# BOOT_JTAG_AUX.net
KiCad netlist of a schematic drawn in Altium Designer
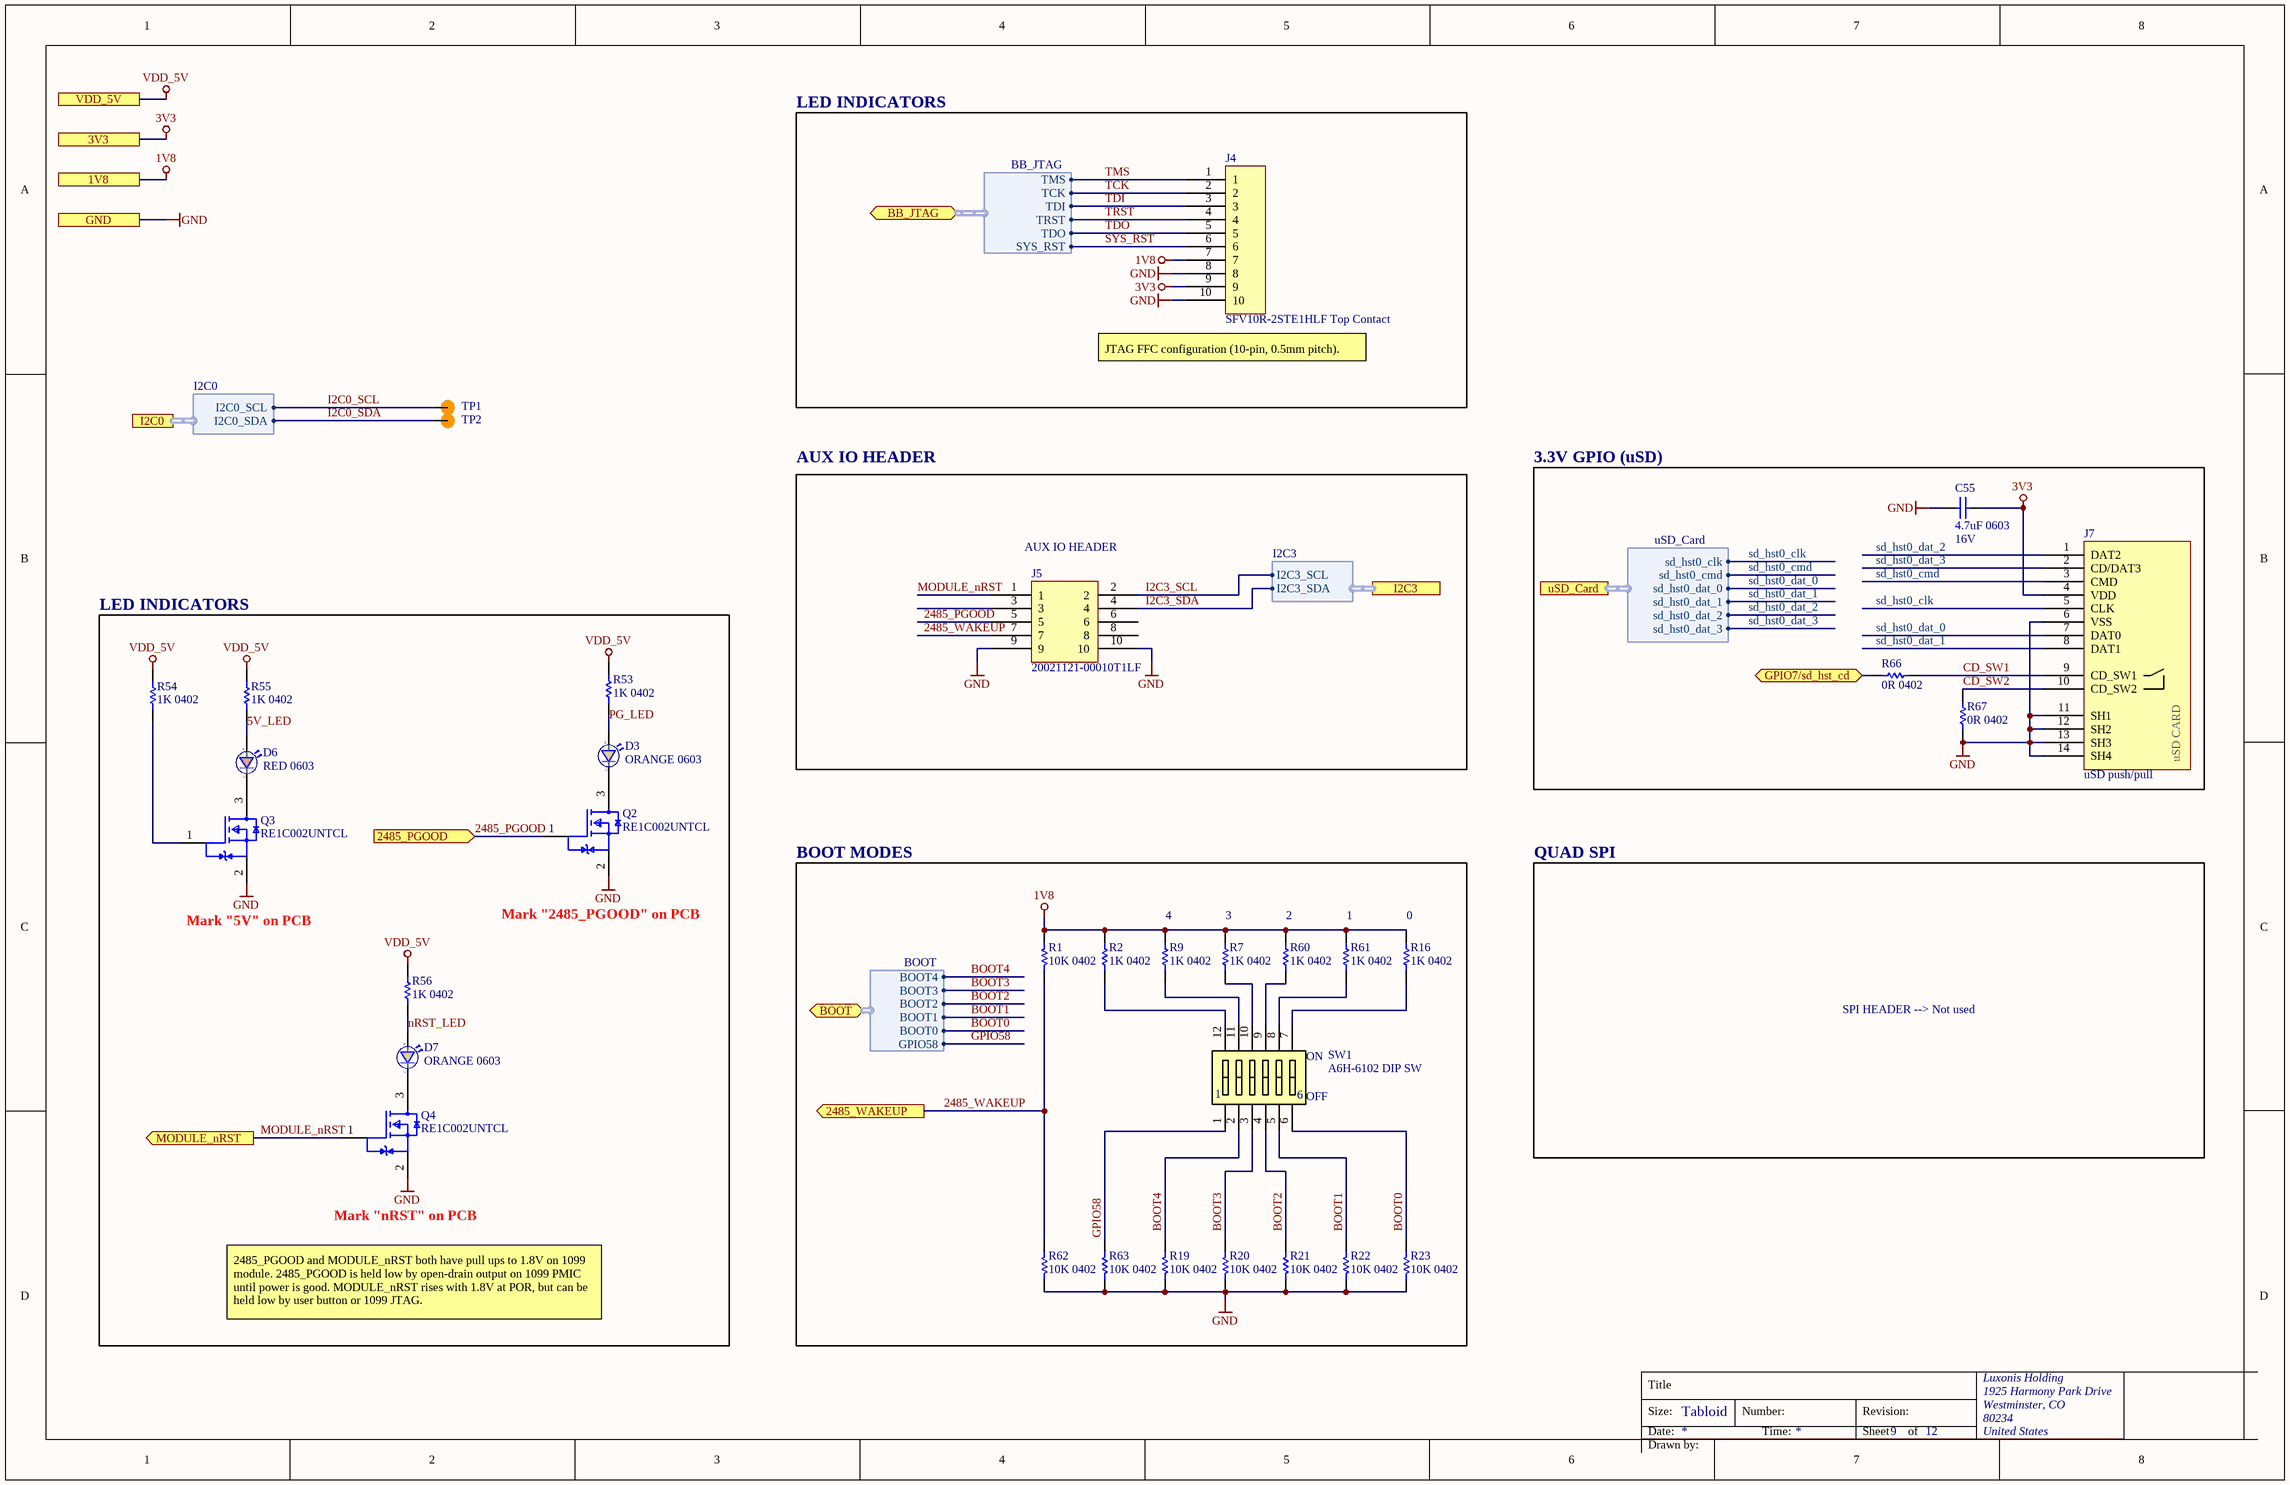
[diagram p0: BOOT_JTAG_AUX.SchDoc]

(export (version "E")
  (design (tool "Eeschema 10.0.6"))
  (components
    (comp (ref "C55")
      (value "4.7uF 0603")
      (footprint "CAP_Altium_Vault_Generic:CAPC0603(1608)100_N")
      (description "CAP CER 4.7UF 16V X5R 0603 10%")
      (fields (field (name "TOLERANCE") "10%") (field (name "VOLTAGE RATING") "16V"))
      (libsource (lib "LuxonisMaster") (part "GRM188R61C475KAAJD"))
    )
    (comp (ref "D3")
      (value "ORANGE 0603")
      (footprint "LuxonisMaster:SML_D1xx8W")
      (description "LED ORANGE DIFFUSED 0603 SMD Orange 605nm LED Indication - Discrete 2.2V 0603 (1608 Metric)")
      (libsource (lib "LuxonisMaster") (part "SML-D12D8WT86"))
    )
    (comp (ref "D6")
      (value "RED 0603")
      (footprint "LuxonisMaster:SML_D1xx8W")
      (description "LED RED DIFFUSED 0603 SMD Red 620nm LED Indication - Discrete 2.2V 0603 (1608 Metric)")
      (libsource (lib "LuxonisMaster") (part "SML-D12U8WT86"))
    )
    (comp (ref "D7")
      (value "ORANGE 0603")
      (footprint "LuxonisMaster:SML_D1xx8W")
      (description "LED ORANGE DIFFUSED 0603 SMD Orange 605nm LED Indication - Discrete 2.2V 0603 (1608 Metric)")
      (libsource (lib "LuxonisMaster") (part "SML-D12D8WT86"))
    )
    (comp (ref "J4")
      (value "SFV10R-2STE1HLF Top Contact")
      (footprint "LuxonisMaster:SFV10R-2STE1HLF")
      (description "CONN FFC TOP 10POS 0.50MM R/A")
      (libsource (lib "LuxonisMaster") (part "SFV10R-2STE1HLF"))
    )
    (comp (ref "J5")
      (value "20021121-00010T1LF")
      (footprint "LuxonisMaster:20021121-00010T1LF")
      (description "CONN HEADER SMD 10POS 1.27MM")
      (libsource (lib "LuxonisMaster") (part "20021121-00010T1LF"))
    )
    (comp (ref "J7")
      (value "uSD push/pull")
      (footprint "LuxonisMaster:104031-0811")
      (description "CONN MICRO SD CARD PUSH-PULL R/A")
      (libsource (lib "LuxonisMaster") (part "104031-0811"))
    )
    (comp (ref "Q2")
      (value "RE1C002UNTCL")
      (footprint "LuxonisMaster:RE1C002UNTCL")
      (description "MOSFET N-CH 20V 0.2A EMT3")
      (libsource (lib "LuxonisMaster") (part "RE1C002UNTCL"))
    )
    (comp (ref "Q3")
      (value "RE1C002UNTCL")
      (footprint "LuxonisMaster:RE1C002UNTCL")
      (description "MOSFET N-CH 20V 0.2A EMT3")
      (libsource (lib "LuxonisMaster") (part "RE1C002UNTCL"))
    )
    (comp (ref "Q4")
      (value "RE1C002UNTCL")
      (footprint "LuxonisMaster:RE1C002UNTCL")
      (description "MOSFET N-CH 20V 0.2A EMT3")
      (libsource (lib "LuxonisMaster") (part "RE1C002UNTCL"))
    )
    (comp (ref "R1")
      (value "10K 0402")
      (footprint "RES_Altium_Vault_Generic:RESC0402(1005)_N")
      (fields (field (name "TOLERANCE") "1%"))
      (libsource (lib "LuxonisMaster") (part "RC0402FR-1310KL"))
    )
    (comp (ref "R2")
      (value "1K 0402")
      (footprint "RES_Altium_Vault_Generic:RESC0402(1005)_N")
      (fields (field (name "TOLERANCE") "1%"))
      (libsource (lib "LuxonisMaster") (part "RC0402FR-071KL"))
    )
    (comp (ref "R7")
      (value "1K 0402")
      (footprint "RES_Altium_Vault_Generic:RESC0402(1005)_N")
      (fields (field (name "TOLERANCE") "1%"))
      (libsource (lib "LuxonisMaster") (part "RC0402FR-071KL"))
    )
    (comp (ref "R9")
      (value "1K 0402")
      (footprint "RES_Altium_Vault_Generic:RESC0402(1005)_N")
      (fields (field (name "TOLERANCE") "1%"))
      (libsource (lib "LuxonisMaster") (part "RC0402FR-071KL"))
    )
    (comp (ref "R16")
      (value "1K 0402")
      (footprint "RES_Altium_Vault_Generic:RESC0402(1005)_N")
      (fields (field (name "TOLERANCE") "1%"))
      (libsource (lib "LuxonisMaster") (part "RC0402FR-071KL"))
    )
    (comp (ref "R19")
      (value "10K 0402")
      (footprint "RES_Altium_Vault_Generic:RESC0402(1005)_N")
      (fields (field (name "TOLERANCE") "1%"))
      (libsource (lib "LuxonisMaster") (part "RC0402FR-1310KL"))
    )
    (comp (ref "R20")
      (value "10K 0402")
      (footprint "RES_Altium_Vault_Generic:RESC0402(1005)_N")
      (fields (field (name "TOLERANCE") "1%"))
      (libsource (lib "LuxonisMaster") (part "RC0402FR-1310KL"))
    )
    (comp (ref "R21")
      (value "10K 0402")
      (footprint "RES_Altium_Vault_Generic:RESC0402(1005)_N")
      (fields (field (name "TOLERANCE") "1%"))
      (libsource (lib "LuxonisMaster") (part "RC0402FR-1310KL"))
    )
    (comp (ref "R22")
      (value "10K 0402")
      (footprint "RES_Altium_Vault_Generic:RESC0402(1005)_N")
      (fields (field (name "TOLERANCE") "1%"))
      (libsource (lib "LuxonisMaster") (part "RC0402FR-1310KL"))
    )
    (comp (ref "R23")
      (value "10K 0402")
      (footprint "RES_Altium_Vault_Generic:RESC0402(1005)_N")
      (fields (field (name "TOLERANCE") "1%"))
      (libsource (lib "LuxonisMaster") (part "RC0402FR-1310KL"))
    )
    (comp (ref "R53")
      (value "1K 0402")
      (footprint "RES_Altium_Vault_Generic:RESC0402(1005)_N")
      (fields (field (name "TOLERANCE") "1%"))
      (libsource (lib "LuxonisMaster") (part "RC0402FR-071KL"))
    )
    (comp (ref "R54")
      (value "1K 0402")
      (footprint "RES_Altium_Vault_Generic:RESC0402(1005)_N")
      (fields (field (name "TOLERANCE") "1%"))
      (libsource (lib "LuxonisMaster") (part "RC0402FR-071KL"))
    )
    (comp (ref "R55")
      (value "1K 0402")
      (footprint "RES_Altium_Vault_Generic:RESC0402(1005)_N")
      (fields (field (name "TOLERANCE") "1%"))
      (libsource (lib "LuxonisMaster") (part "RC0402FR-071KL"))
    )
    (comp (ref "R56")
      (value "1K 0402")
      (footprint "RES_Altium_Vault_Generic:RESC0402(1005)_N")
      (fields (field (name "TOLERANCE") "1%"))
      (libsource (lib "LuxonisMaster") (part "RC0402FR-071KL"))
    )
    (comp (ref "R60")
      (value "1K 0402")
      (footprint "RES_Altium_Vault_Generic:RESC0402(1005)_N")
      (fields (field (name "TOLERANCE") "1%"))
      (libsource (lib "LuxonisMaster") (part "RC0402FR-071KL"))
    )
    (comp (ref "R61")
      (value "1K 0402")
      (footprint "RES_Altium_Vault_Generic:RESC0402(1005)_N")
      (fields (field (name "TOLERANCE") "1%"))
      (libsource (lib "LuxonisMaster") (part "RC0402FR-071KL"))
    )
    (comp (ref "R62")
      (value "10K 0402")
      (footprint "RES_Altium_Vault_Generic:RESC0402(1005)_N")
      (fields (field (name "TOLERANCE") "1%"))
      (libsource (lib "LuxonisMaster") (part "RC0402FR-1310KL"))
    )
    (comp (ref "R63")
      (value "10K 0402")
      (footprint "RES_Altium_Vault_Generic:RESC0402(1005)_N")
      (fields (field (name "TOLERANCE") "1%"))
      (libsource (lib "LuxonisMaster") (part "RC0402FR-1310KL"))
    )
    (comp (ref "R66")
      (value "0R 0402")
      (footprint "RES_Altium_Vault_Generic:RESC0402(1005)_N")
      (description "RES SMD 0 OHM JUMPER 1/16W 0402")
      (fields (field (name "TOLERANCE") "5%"))
      (libsource (lib "LuxonisMaster") (part "CRCW04020000Z0ED"))
    )
    (comp (ref "R67")
      (value "0R 0402")
      (footprint "RES_Altium_Vault_Generic:RESC0402(1005)_N")
      (description "RES SMD 0 OHM JUMPER 1/16W 0402")
      (fields (field (name "TOLERANCE") "5%"))
      (libsource (lib "LuxonisMaster") (part "CRCW04020000Z0ED"))
    )
    (comp (ref "SW1")
      (value "A6H-6102 DIP SW")
      (footprint "LuxonisMaster:A6H-610x")
      (description "SWITCH SLIDE DIP SPST 25MA 24V (SEALED)")
      (libsource (lib "LuxonisMaster") (part "A6H-6102"))
    )
    (comp (ref "TP1")
      (value "TP100_200_NS")
      (footprint "LuxonisMaster:TP100_200_NS")
      (libsource (lib "LuxonisMaster") (part "TEST_POINT"))
    )
    (comp (ref "TP2")
      (value "TP100_200_NS")
      (footprint "LuxonisMaster:TP100_200_NS")
      (libsource (lib "LuxonisMaster") (part "TEST_POINT"))
    )
  )
  (nets
    (net (code "6") (name "/5V_LED") (class "Default")
      (node (ref "D6") (pin "2") (pinfunction "A_2") (pintype "passive"))
      (node (ref "R55") (pin "1") (pinfunction "1_1") (pintype "passive"))
    )
    (net (code "7") (name "/2485_PGOOD") (class "Default")
      (node (ref "J5") (pin "5") (pinfunction "5_5") (pintype "passive"))
      (node (ref "Q2") (pin "1") (pinfunction "Gate_1") (pintype "passive"))
    )
    (net (code "8") (name "/2485_WAKEUP") (class "Default")
      (node (ref "J5") (pin "7") (pinfunction "7_7") (pintype "passive"))
      (node (ref "R1") (pin "2") (pinfunction "2_2") (pintype "passive"))
      (node (ref "R62") (pin "1") (pinfunction "1_1") (pintype "passive"))
    )
    (net (code "9") (name "/BOOT0") (class "Default")
      (node (ref "R23") (pin "1") (pinfunction "1_1") (pintype "passive"))
      (node (ref "SW1") (pin "6") (pinfunction "6_6") (pintype "passive"))
    )
    (net (code "10") (name "/BOOT1") (class "Default")
      (node (ref "R22") (pin "1") (pinfunction "1_1") (pintype "passive"))
      (node (ref "SW1") (pin "5") (pinfunction "5_5") (pintype "passive"))
    )
    (net (code "11") (name "/BOOT2") (class "Default")
      (node (ref "R21") (pin "1") (pinfunction "1_1") (pintype "passive"))
      (node (ref "SW1") (pin "4") (pinfunction "4_4") (pintype "passive"))
    )
    (net (code "12") (name "/BOOT3") (class "Default")
      (node (ref "R20") (pin "1") (pinfunction "1_1") (pintype "passive"))
      (node (ref "SW1") (pin "3") (pinfunction "3_3") (pintype "passive"))
    )
    (net (code "13") (name "/BOOT4") (class "Default")
      (node (ref "R19") (pin "1") (pinfunction "1_1") (pintype "passive"))
      (node (ref "SW1") (pin "2") (pinfunction "2_2") (pintype "passive"))
    )
    (net (code "14") (name "/CD_SW1") (class "Default")
      (node (ref "J7") (pin "9") (pinfunction "CD_SW1_9") (pintype "passive"))
      (node (ref "R66") (pin "1") (pinfunction "1_1") (pintype "passive"))
    )
    (net (code "15") (name "/CD_SW2") (class "Default")
      (node (ref "J7") (pin "10") (pinfunction "CD_SW2_10") (pintype "passive"))
      (node (ref "R67") (pin "2") (pinfunction "2_2") (pintype "passive"))
    )
    (net (code "16") (name "/GPIO7{slash}sd_hst_cd") (class "Default")
      (node (ref "R66") (pin "2") (pinfunction "2_2") (pintype "passive"))
    )
    (net (code "17") (name "/GPIO58") (class "Default")
      (node (ref "R63") (pin "1") (pinfunction "1_1") (pintype "passive"))
      (node (ref "SW1") (pin "1") (pinfunction "1_1") (pintype "passive"))
    )
    (net (code "18") (name "/I2C0_SCL") (class "Default") (node (ref "TP1") (pin "1") (pintype "passive")))
    (net (code "19") (name "/I2C0_SDA") (class "Default") (node (ref "TP2") (pin "1") (pintype "passive")))
    (net (code "20") (name "/I2C3_SCL") (class "Default")
      (node (ref "J5") (pin "2") (pinfunction "2_2") (pintype "passive"))
    )
    (net (code "21") (name "/I2C3_SDA") (class "Default")
      (node (ref "J5") (pin "4") (pinfunction "4_4") (pintype "passive"))
    )
    (net (code "22") (name "/MODULE_nRST") (class "Default")
      (node (ref "J5") (pin "1") (pinfunction "1_1") (pintype "passive"))
      (node (ref "Q4") (pin "1") (pinfunction "Gate_1") (pintype "passive"))
    )
    (net (code "23") (name "/PG_LED") (class "Default")
      (node (ref "D3") (pin "2") (pinfunction "A_2") (pintype "passive"))
      (node (ref "R53") (pin "1") (pinfunction "1_1") (pintype "passive"))
    )
    (net (code "24") (name "/SYS_RST") (class "Default")
      (node (ref "J4") (pin "6") (pinfunction "6_6") (pintype "passive"))
    )
    (net (code "25") (name "/TCK") (class "Default")
      (node (ref "J4") (pin "2") (pinfunction "2_2") (pintype "passive"))
    )
    (net (code "26") (name "/TDI") (class "Default")
      (node (ref "J4") (pin "3") (pinfunction "3_3") (pintype "passive"))
    )
    (net (code "27") (name "/TDO") (class "Default")
      (node (ref "J4") (pin "5") (pinfunction "5_5") (pintype "passive"))
    )
    (net (code "28") (name "/TMS") (class "Default")
      (node (ref "J4") (pin "1") (pinfunction "1_1") (pintype "passive"))
    )
    (net (code "29") (name "/TRST") (class "Default")
      (node (ref "J4") (pin "4") (pinfunction "4_4") (pintype "passive"))
    )
    (net (code "30") (name "/nRST_LED") (class "Default")
      (node (ref "D7") (pin "2") (pinfunction "A_2") (pintype "passive"))
      (node (ref "R56") (pin "1") (pinfunction "1_1") (pintype "passive"))
    )
    (net (code "31") (name "/sd_hst0_clk") (class "Default")
      (node (ref "J7") (pin "5") (pinfunction "CLK_5") (pintype "passive"))
    )
    (net (code "32") (name "/sd_hst0_cmd") (class "Default")
      (node (ref "J7") (pin "3") (pinfunction "CMD_3") (pintype "passive"))
    )
    (net (code "33") (name "/sd_hst0_dat_0") (class "Default")
      (node (ref "J7") (pin "7") (pinfunction "DAT0_7") (pintype "passive"))
    )
    (net (code "34") (name "/sd_hst0_dat_1") (class "Default")
      (node (ref "J7") (pin "8") (pinfunction "DAT1_8") (pintype "passive"))
    )
    (net (code "35") (name "/sd_hst0_dat_2") (class "Default")
      (node (ref "J7") (pin "1") (pinfunction "DAT2_1") (pintype "passive"))
    )
    (net (code "36") (name "/sd_hst0_dat_3") (class "Default")
      (node (ref "J7") (pin "2") (pinfunction "CD/DAT3_2") (pintype "passive"))
    )
    (net (code "42") (name "1V8") (class "Default")
      (node (ref "J4") (pin "7") (pinfunction "7_7") (pintype "passive"))
      (node (ref "R1") (pin "1") (pinfunction "1_1") (pintype "passive"))
      (node (ref "R16") (pin "2") (pinfunction "2_2") (pintype "passive"))
      (node (ref "R2") (pin "2") (pinfunction "2_2") (pintype "passive"))
      (node (ref "R60") (pin "2") (pinfunction "2_2") (pintype "passive"))
      (node (ref "R61") (pin "2") (pinfunction "2_2") (pintype "passive"))
      (node (ref "R7") (pin "2") (pinfunction "2_2") (pintype "passive"))
      (node (ref "R9") (pin "2") (pinfunction "2_2") (pintype "passive"))
    )
    (net (code "43") (name "3V3") (class "Default")
      (node (ref "C55") (pin "2") (pinfunction "2_2") (pintype "passive"))
      (node (ref "J4") (pin "9") (pinfunction "9_9") (pintype "passive"))
      (node (ref "J7") (pin "4") (pinfunction "VDD_4") (pintype "passive"))
    )
    (net (code "44") (name "GND") (class "Default")
      (node (ref "C55") (pin "1") (pinfunction "1_1") (pintype "passive"))
      (node (ref "J4") (pin "10") (pinfunction "10_10") (pintype "passive"))
      (node (ref "J4") (pin "8") (pinfunction "8_8") (pintype "passive"))
      (node (ref "J5") (pin "10") (pinfunction "10_10") (pintype "passive"))
      (node (ref "J5") (pin "9") (pinfunction "9_9") (pintype "passive"))
      (node (ref "J7") (pin "11") (pinfunction "SH1_11") (pintype "passive"))
      (node (ref "J7") (pin "12") (pinfunction "SH2_12") (pintype "passive"))
      (node (ref "J7") (pin "13") (pinfunction "SH3_13") (pintype "passive"))
      (node (ref "J7") (pin "14") (pinfunction "SH4_14") (pintype "passive"))
      (node (ref "J7") (pin "6") (pinfunction "VSS_6") (pintype "passive"))
      (node (ref "Q2") (pin "2") (pinfunction "Source_2") (pintype "passive"))
      (node (ref "Q3") (pin "2") (pinfunction "Source_2") (pintype "passive"))
      (node (ref "Q4") (pin "2") (pinfunction "Source_2") (pintype "passive"))
      (node (ref "R19") (pin "2") (pinfunction "2_2") (pintype "passive"))
      (node (ref "R20") (pin "2") (pinfunction "2_2") (pintype "passive"))
      (node (ref "R21") (pin "2") (pinfunction "2_2") (pintype "passive"))
      (node (ref "R22") (pin "2") (pinfunction "2_2") (pintype "passive"))
      (node (ref "R23") (pin "2") (pinfunction "2_2") (pintype "passive"))
      (node (ref "R62") (pin "2") (pinfunction "2_2") (pintype "passive"))
      (node (ref "R63") (pin "2") (pinfunction "2_2") (pintype "passive"))
      (node (ref "R67") (pin "1") (pinfunction "1_1") (pintype "passive"))
    )
    (net (code "45") (name "Net-(D3-C)") (class "Default")
      (node (ref "D3") (pin "1") (pinfunction "C_1") (pintype "passive"))
      (node (ref "Q2") (pin "3") (pinfunction "Drain_3") (pintype "passive"))
    )
    (net (code "46") (name "Net-(D6-C)") (class "Default")
      (node (ref "D6") (pin "1") (pinfunction "C_1") (pintype "passive"))
      (node (ref "Q3") (pin "3") (pinfunction "Drain_3") (pintype "passive"))
    )
    (net (code "47") (name "Net-(D7-C)") (class "Default")
      (node (ref "D7") (pin "1") (pinfunction "C_1") (pintype "passive"))
      (node (ref "Q4") (pin "3") (pinfunction "Drain_3") (pintype "passive"))
    )
    (net (code "48") (name "Net-(Q3-Gate)") (class "Default")
      (node (ref "Q3") (pin "1") (pinfunction "Gate_1") (pintype "passive"))
      (node (ref "R54") (pin "1") (pinfunction "1_1") (pintype "passive"))
    )
    (net (code "49") (name "Net-(R2-Pad1)") (class "Default")
      (node (ref "R2") (pin "1") (pinfunction "1_1") (pintype "passive"))
      (node (ref "SW1") (pin "12") (pinfunction "12_12") (pintype "passive"))
    )
    (net (code "50") (name "Net-(R7-Pad1)") (class "Default")
      (node (ref "R7") (pin "1") (pinfunction "1_1") (pintype "passive"))
      (node (ref "SW1") (pin "10") (pinfunction "10_10") (pintype "passive"))
    )
    (net (code "51") (name "Net-(R9-Pad1)") (class "Default")
      (node (ref "R9") (pin "1") (pinfunction "1_1") (pintype "passive"))
      (node (ref "SW1") (pin "11") (pinfunction "11_11") (pintype "passive"))
    )
    (net (code "52") (name "Net-(R16-Pad1)") (class "Default")
      (node (ref "R16") (pin "1") (pinfunction "1_1") (pintype "passive"))
      (node (ref "SW1") (pin "7") (pinfunction "7_7") (pintype "passive"))
    )
    (net (code "53") (name "Net-(R60-Pad1)") (class "Default")
      (node (ref "R60") (pin "1") (pinfunction "1_1") (pintype "passive"))
      (node (ref "SW1") (pin "9") (pinfunction "9_9") (pintype "passive"))
    )
    (net (code "54") (name "Net-(R61-Pad1)") (class "Default")
      (node (ref "R61") (pin "1") (pinfunction "1_1") (pintype "passive"))
      (node (ref "SW1") (pin "8") (pinfunction "8_8") (pintype "passive"))
    )
    (net (code "55") (name "VDD_5V") (class "Default")
      (node (ref "R53") (pin "2") (pinfunction "2_2") (pintype "passive"))
      (node (ref "R54") (pin "2") (pinfunction "2_2") (pintype "passive"))
      (node (ref "R55") (pin "2") (pinfunction "2_2") (pintype "passive"))
      (node (ref "R56") (pin "2") (pinfunction "2_2") (pintype "passive"))
    )
    (net (code "56") (name "unconnected-(J5-Pad3)") (class "Default")
      (node (ref "J5") (pin "3") (pinfunction "3_3") (pintype "passive"))
    )
    (net (code "57") (name "unconnected-(J5-Pad6)") (class "Default")
      (node (ref "J5") (pin "6") (pinfunction "6_6") (pintype "passive"))
    )
    (net (code "58") (name "unconnected-(J5-Pad8)") (class "Default")
      (node (ref "J5") (pin "8") (pinfunction "8_8") (pintype "passive"))
    )
  )
)
